# Probatio5Pins_v0_0_2.net
KiCad netlist of a schematic drawn in EAGLE
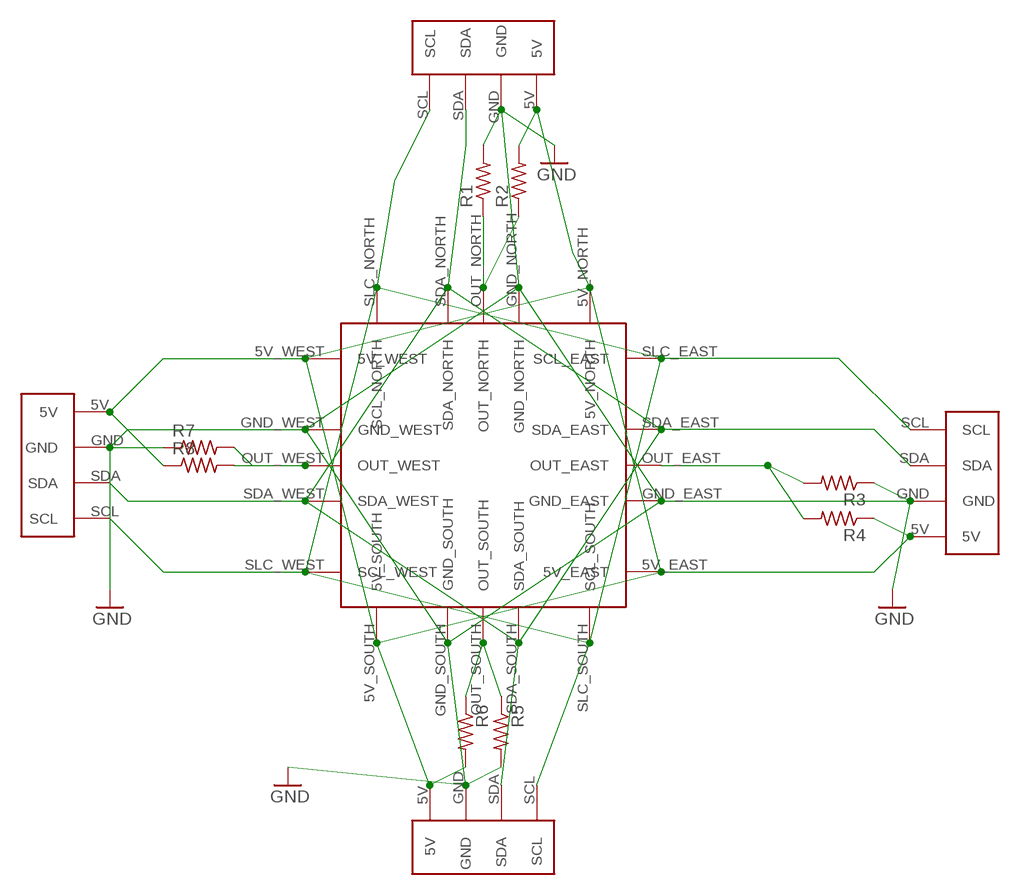
[diagram p0: schematic, sheet 1]

(export (version "E")
  (design (tool "Eeschema 10.0.6"))
  (components
    (comp (ref "CENTER1")
      (value "CONNECTORS_PIN_DEVICE")
      (footprint "eagle-import:CONNECTORS_PIN")
      (libsource (lib "eagle-import") (part "CONNECTORS_PIN_DEVICE"))
    )
    (comp (ref "R1")
      (value "R-US_R0805")
      (footprint "eagle-import:R0805")
      (libsource (lib "eagle-import") (part "R-US_R0805"))
    )
    (comp (ref "R2")
      (value "R-US_R0805")
      (footprint "eagle-import:R0805")
      (libsource (lib "eagle-import") (part "R-US_R0805"))
    )
    (comp (ref "R3")
      (value "R-US_R0805")
      (footprint "eagle-import:R0805")
      (libsource (lib "eagle-import") (part "R-US_R0805"))
    )
    (comp (ref "R4")
      (value "R-US_R0805")
      (footprint "eagle-import:R0805")
      (libsource (lib "eagle-import") (part "R-US_R0805"))
    )
    (comp (ref "R5")
      (value "R-US_R0805")
      (footprint "eagle-import:R0805")
      (libsource (lib "eagle-import") (part "R-US_R0805"))
    )
    (comp (ref "R6")
      (value "R-US_R0805")
      (footprint "eagle-import:R0805")
      (libsource (lib "eagle-import") (part "R-US_R0805"))
    )
    (comp (ref "R7")
      (value "R-US_R0805")
      (footprint "eagle-import:R0805")
      (libsource (lib "eagle-import") (part "R-US_R0805"))
    )
    (comp (ref "R8")
      (value "R-US_R0805")
      (footprint "eagle-import:R0805")
      (libsource (lib "eagle-import") (part "R-US_R0805"))
    )
    (comp (ref "U$1")
      (value "FOUR_SIDE_PINS")
      (footprint "eagle-import:FOUR_SIDE_PINS")
      (libsource (lib "eagle-import") (part "FOUR_SIDE_PINS"))
    )
    (comp (ref "U$2")
      (value "FOUR_SIDE_PINS")
      (footprint "eagle-import:FOUR_SIDE_PINS")
      (libsource (lib "eagle-import") (part "FOUR_SIDE_PINS"))
    )
    (comp (ref "U$3")
      (value "FOUR_SIDE_PINS")
      (footprint "eagle-import:FOUR_SIDE_PINS")
      (libsource (lib "eagle-import") (part "FOUR_SIDE_PINS"))
    )
    (comp (ref "U$4")
      (value "FOUR_SIDE_PINS")
      (footprint "eagle-import:FOUR_SIDE_PINS")
      (libsource (lib "eagle-import") (part "FOUR_SIDE_PINS"))
    )
  )
  (nets
    (net (code "1") (name "GND") (class "Default")
      (node (ref "CENTER1") (pin "GND_EAST") (pinfunction "GND_EAST_GND_EAST") (pintype "bidirectional"))
      (node (ref "CENTER1") (pin "GND_NORTH") (pinfunction "GND_NORTH_GND_NORTH") (pintype "bidirectional"))
      (node (ref "CENTER1") (pin "GND_SOUTH") (pinfunction "GND_SOUTH_GND_SOUTH") (pintype "bidirectional"))
      (node (ref "CENTER1") (pin "GND_WEST") (pinfunction "GND_WEST_GND_WEST") (pintype "bidirectional"))
      (node (ref "R1") (pin "2") (pinfunction "2_2") (pintype "passive"))
      (node (ref "R3") (pin "1") (pinfunction "1_1") (pintype "passive"))
      (node (ref "R5") (pin "2") (pinfunction "2_2") (pintype "passive"))
      (node (ref "R7") (pin "1") (pinfunction "1_1") (pintype "passive"))
      (node (ref "U$1") (pin "GND") (pinfunction "GND_GND") (pintype "bidirectional"))
      (node (ref "U$2") (pin "GND") (pinfunction "GND_GND") (pintype "bidirectional"))
      (node (ref "U$3") (pin "GND") (pinfunction "GND_GND") (pintype "bidirectional"))
      (node (ref "U$4") (pin "GND") (pinfunction "GND_GND") (pintype "bidirectional"))
    )
    (net (code "2") (name "Net-(CENTER1-Pad5V_EAST)") (class "Default")
      (node (ref "CENTER1") (pin "5V_EAST") (pinfunction "5V_EAST_5V_EAST") (pintype "bidirectional"))
      (node (ref "CENTER1") (pin "5V_NORTH") (pinfunction "5V_NORTH_5V_NORTH") (pintype "bidirectional"))
      (node (ref "CENTER1") (pin "5V_SOUTH") (pinfunction "5V_SOUTH_5V_SOUTH") (pintype "bidirectional"))
      (node (ref "CENTER1") (pin "5V_WEST") (pinfunction "5V_WEST_5V_WEST") (pintype "bidirectional"))
      (node (ref "R2") (pin "2") (pinfunction "2_2") (pintype "passive"))
      (node (ref "R4") (pin "1") (pinfunction "1_1") (pintype "passive"))
      (node (ref "R6") (pin "2") (pinfunction "2_2") (pintype "passive"))
      (node (ref "R8") (pin "1") (pinfunction "1_1") (pintype "passive"))
      (node (ref "U$1") (pin "5V") (pinfunction "5V_5V") (pintype "bidirectional"))
      (node (ref "U$2") (pin "5V") (pinfunction "5V_5V") (pintype "bidirectional"))
      (node (ref "U$3") (pin "5V") (pinfunction "5V_5V") (pintype "bidirectional"))
      (node (ref "U$4") (pin "5V") (pinfunction "5V_5V") (pintype "bidirectional"))
    )
    (net (code "3") (name "Net-(CENTER1-PadOUT_EAST)") (class "Default")
      (node (ref "CENTER1") (pin "OUT_EAST") (pinfunction "OUT_EAST_OUT_EAST") (pintype "bidirectional"))
      (node (ref "R3") (pin "2") (pinfunction "2_2") (pintype "passive"))
      (node (ref "R4") (pin "2") (pinfunction "2_2") (pintype "passive"))
    )
    (net (code "4") (name "Net-(CENTER1-PadOUT_NORTH)") (class "Default")
      (node (ref "CENTER1") (pin "OUT_NORTH") (pinfunction "OUT_NORTH_OUT_NORTH") (pintype "bidirectional"))
      (node (ref "R1") (pin "1") (pinfunction "1_1") (pintype "passive"))
      (node (ref "R2") (pin "1") (pinfunction "1_1") (pintype "passive"))
    )
    (net (code "5") (name "Net-(CENTER1-PadOUT_SOUTH)") (class "Default")
      (node (ref "CENTER1") (pin "OUT_SOUTH") (pinfunction "OUT_SOUTH_OUT_SOUTH") (pintype "bidirectional"))
      (node (ref "R5") (pin "1") (pinfunction "1_1") (pintype "passive"))
      (node (ref "R6") (pin "1") (pinfunction "1_1") (pintype "passive"))
    )
    (net (code "6") (name "Net-(CENTER1-PadOUT_WEST)") (class "Default")
      (node (ref "CENTER1") (pin "OUT_WEST") (pinfunction "OUT_WEST_OUT_WEST") (pintype "bidirectional"))
      (node (ref "R7") (pin "2") (pinfunction "2_2") (pintype "passive"))
      (node (ref "R8") (pin "2") (pinfunction "2_2") (pintype "passive"))
    )
    (net (code "7") (name "Net-(CENTER1-PadSDA_EAST)") (class "Default")
      (node (ref "CENTER1") (pin "SDA_EAST") (pinfunction "SDA_EAST_SDA_EAST") (pintype "bidirectional"))
      (node (ref "CENTER1") (pin "SDA_NORTH") (pinfunction "SDA_NORTH_SDA_NORTH") (pintype "bidirectional"))
      (node (ref "CENTER1") (pin "SDA_SOUTH") (pinfunction "SDA_SOUTH_SDA_SOUTH") (pintype "bidirectional"))
      (node (ref "CENTER1") (pin "SDA_WEST") (pinfunction "SDA_WEST_SDA_WEST") (pintype "bidirectional"))
      (node (ref "U$1") (pin "SDA") (pinfunction "SDA_SDA") (pintype "bidirectional"))
      (node (ref "U$2") (pin "SDA") (pinfunction "SDA_SDA") (pintype "bidirectional"))
      (node (ref "U$3") (pin "SDA") (pinfunction "SDA_SDA") (pintype "bidirectional"))
      (node (ref "U$4") (pin "SDA") (pinfunction "SDA_SDA") (pintype "bidirectional"))
    )
    (net (code "8") (name "Net-(CENTER1-SCL_EAST)") (class "Default")
      (node (ref "CENTER1") (pin "SLC_EAST") (pinfunction "SCL_EAST_SLC_EAST") (pintype "bidirectional"))
      (node (ref "CENTER1") (pin "SLC_NORTH") (pinfunction "SCL_NORTH_SLC_NORTH") (pintype "bidirectional"))
      (node (ref "CENTER1") (pin "SLC_SOUTH") (pinfunction "SCL_SOUTH_SLC_SOUTH") (pintype "bidirectional"))
      (node (ref "CENTER1") (pin "SLC_WEST") (pinfunction "SCL_WEST_SLC_WEST") (pintype "bidirectional"))
      (node (ref "U$1") (pin "SCL") (pinfunction "SCL_SCL") (pintype "bidirectional"))
      (node (ref "U$2") (pin "SCL") (pinfunction "SCL_SCL") (pintype "bidirectional"))
      (node (ref "U$3") (pin "SCL") (pinfunction "SCL_SCL") (pintype "bidirectional"))
      (node (ref "U$4") (pin "SCL") (pinfunction "SCL_SCL") (pintype "bidirectional"))
    )
  )
)
